# bathroomIndicator.net
KiCad netlist of a schematic drawn in EAGLE
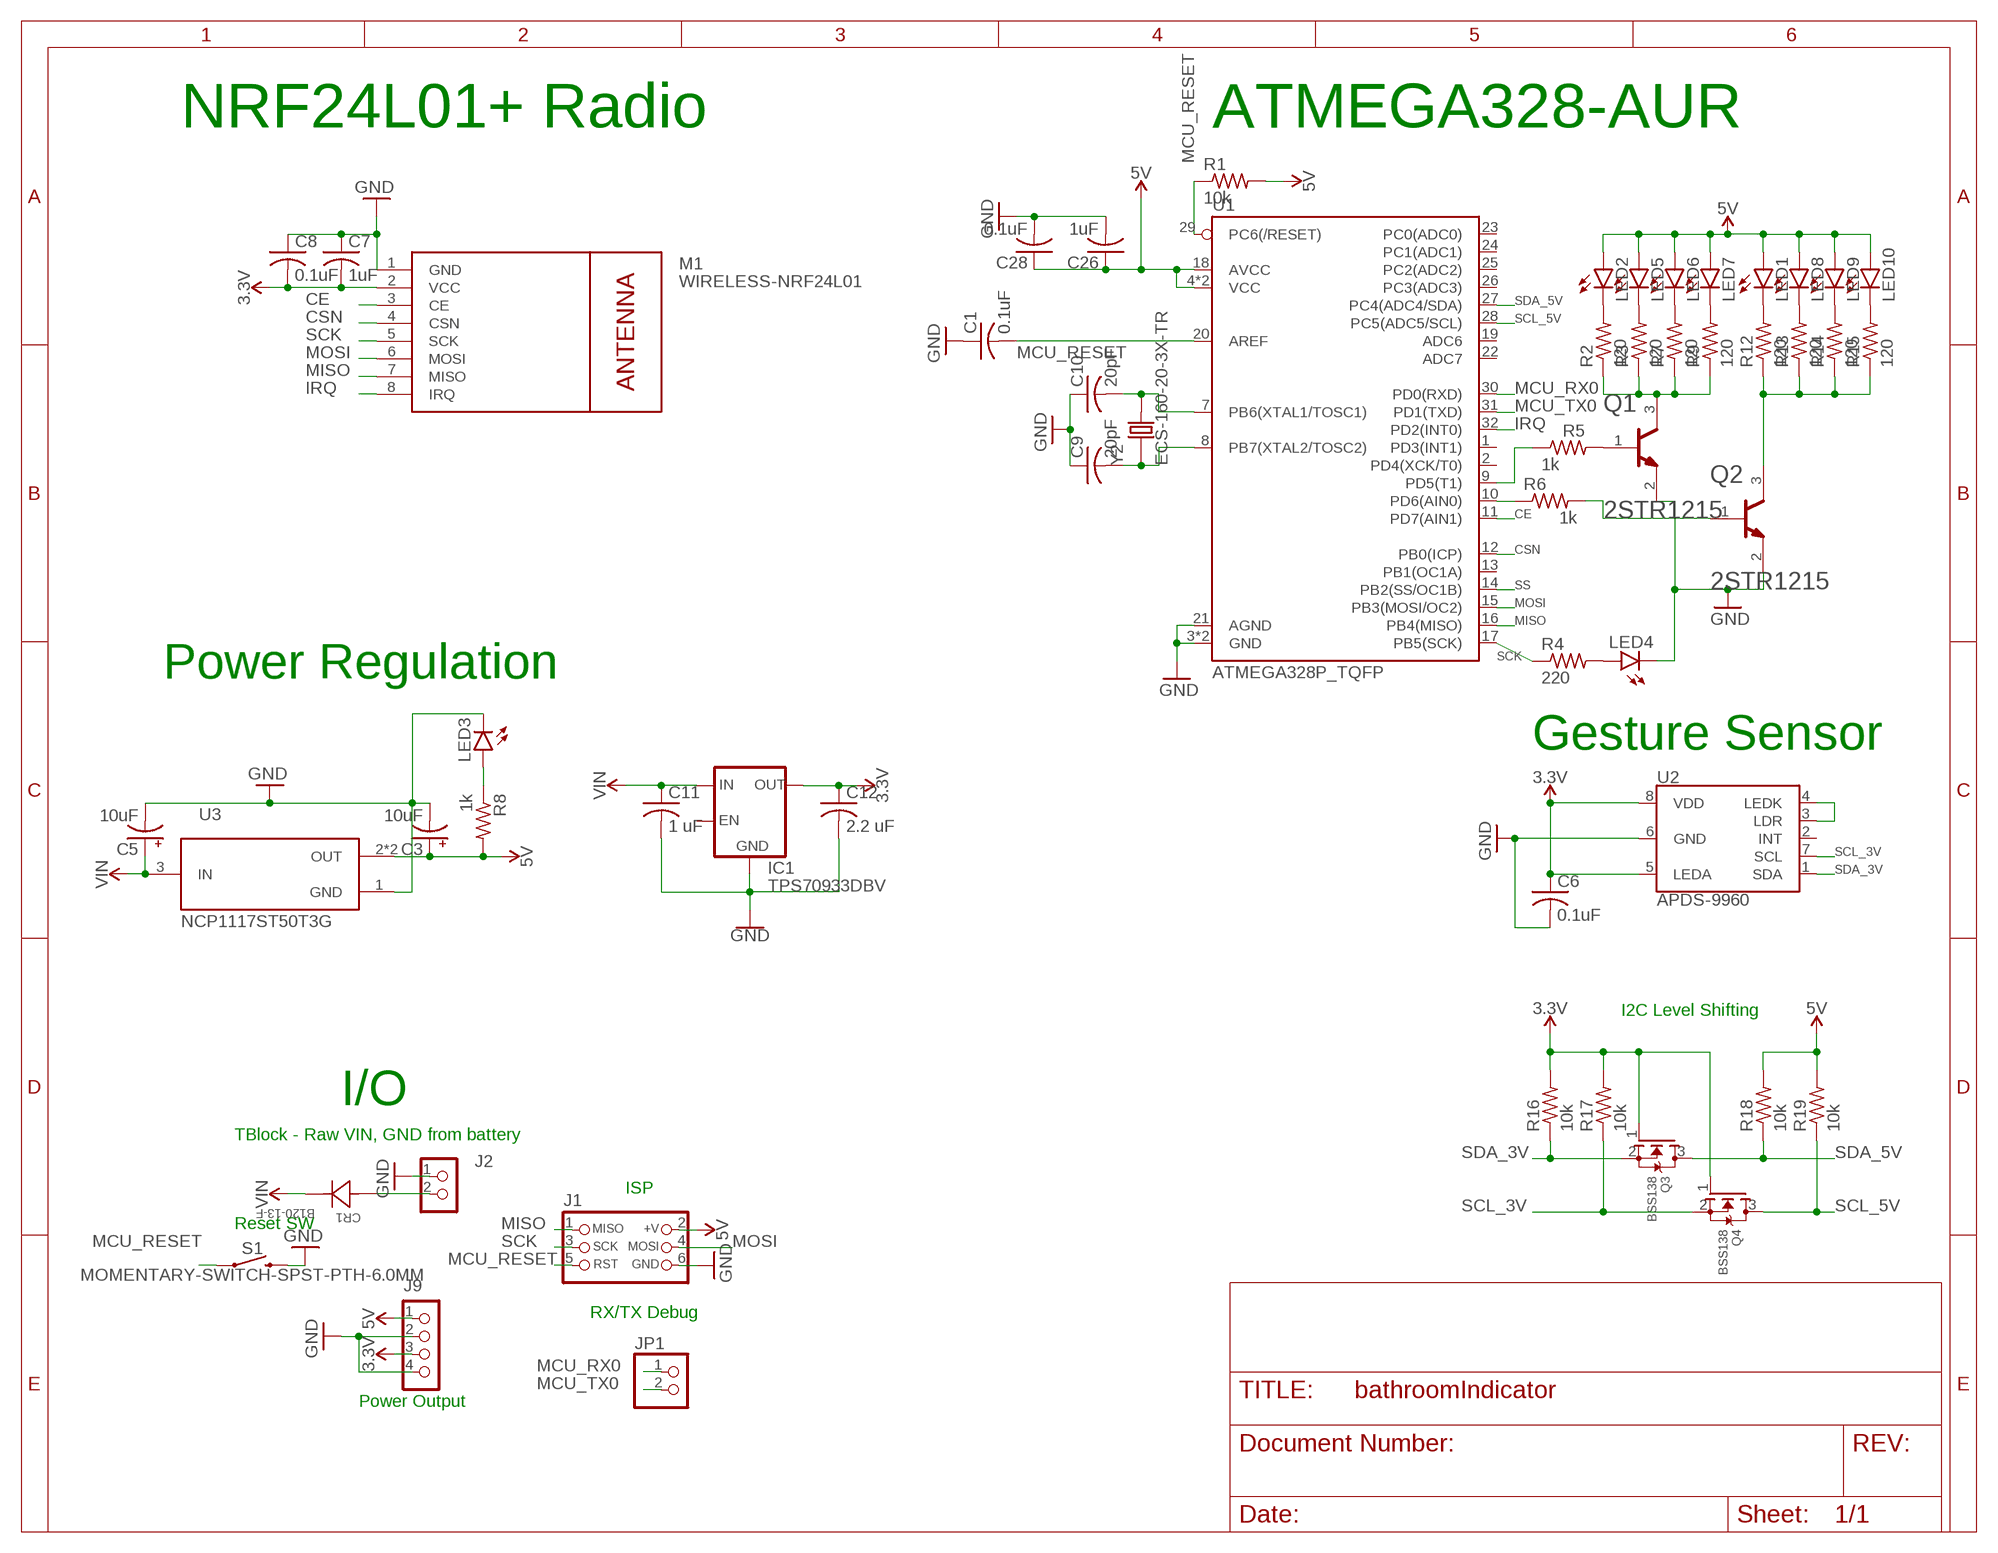
[diagram p0: schematic, sheet 1]

(export (version "E")
  (design (tool "Eeschema 10.0.6"))
  (components
    (comp (ref "C1")
      (value "0.1uF")
      (footprint "eagle-import:C0805")
      (libsource (lib "eagle-import") (part "C-USC0805"))
    )
    (comp (ref "C3")
      (value "10uF")
      (footprint "eagle-import:B_3528-21W")
      (libsource (lib "eagle-import") (part "CPOL-USB/3528-21W"))
    )
    (comp (ref "C5")
      (value "10uF")
      (footprint "eagle-import:B_3528-21W")
      (libsource (lib "eagle-import") (part "CPOL-USB/3528-21W"))
    )
    (comp (ref "C6")
      (value "0.1uF")
      (footprint "eagle-import:C0805")
      (libsource (lib "eagle-import") (part "C-USC0805"))
    )
    (comp (ref "C7")
      (value "1uF")
      (footprint "eagle-import:C0805")
      (libsource (lib "eagle-import") (part "C-USC0805"))
    )
    (comp (ref "C8")
      (value "0.1uF")
      (footprint "eagle-import:C0805")
      (libsource (lib "eagle-import") (part "C-USC0805"))
    )
    (comp (ref "C9")
      (value "20pF")
      (footprint "eagle-import:C0805")
      (libsource (lib "eagle-import") (part "C-USC0805"))
    )
    (comp (ref "C10")
      (value "20pF")
      (footprint "eagle-import:C0805")
      (libsource (lib "eagle-import") (part "C-USC0805"))
    )
    (comp (ref "C11")
      (value "1 uF")
      (footprint "eagle-import:C0805")
      (libsource (lib "eagle-import") (part "C-USC0805"))
    )
    (comp (ref "C12")
      (value "2.2 uF")
      (footprint "eagle-import:C0805")
      (libsource (lib "eagle-import") (part "C-USC0805"))
    )
    (comp (ref "C26")
      (value "1uF")
      (footprint "eagle-import:C0805")
      (libsource (lib "eagle-import") (part "C-USC0805"))
    )
    (comp (ref "C28")
      (value "0.1uF")
      (footprint "eagle-import:C0805")
      (libsource (lib "eagle-import") (part "C-USC0805"))
    )
    (comp (ref "CR1")
      (value "B120-13-F")
      (footprint "eagle-import:SMA_DIO")
      (libsource (lib "eagle-import") (part "B120-13-F"))
    )
    (comp (ref "IC1")
      (value "TPS70933DBV")
      (footprint "eagle-import:SOT23-5")
      (fields (field (name "MF") "Texas Instruments") (field (name "MPN") "TPS70933DBVT"))
      (libsource (lib "eagle-import") (part "TPS709DBV33"))
    )
    (comp (ref "J1")
      (value "CON_HEADER_PRG_AVR_ICSP-PTH")
      (footprint "eagle-import:HEADER_PRG_2X03")
      (libsource (lib "eagle-import") (part "CON_HEADER_PRG_AVR_ICSP-PTH"))
    )
    (comp (ref "J2")
      (value "CON_TERMINAL_BLOCK_02-5MM")
      (footprint "eagle-import:TERMINAL_BLOCK_2P_5")
      (libsource (lib "eagle-import") (part "CON_TERMINAL_BLOCK_02-5MM"))
    )
    (comp (ref "J9")
      (value "CON_HEADER_1X04")
      (footprint "eagle-import:M1X4")
      (libsource (lib "eagle-import") (part "CON_HEADER_1X04"))
    )
    (comp (ref "JP1")
      (value "HEADER-1X2ROUND")
      (footprint "eagle-import:1X02_ROUND")
      (libsource (lib "eagle-import") (part "HEADER-1X2ROUND"))
    )
    (comp (ref "LED1")
      (value "LED5MM")
      (footprint "eagle-import:LED5MM")
      (libsource (lib "eagle-import") (part "LED5MM"))
    )
    (comp (ref "LED2")
      (value "LED5MM")
      (footprint "eagle-import:LED5MM")
      (libsource (lib "eagle-import") (part "LED5MM"))
    )
    (comp (ref "LED3")
      (value "LEDSML0805")
      (footprint "eagle-import:SML0805")
      (libsource (lib "eagle-import") (part "LEDSML0805"))
    )
    (comp (ref "LED4")
      (value "LEDSML0805")
      (footprint "eagle-import:SML0805")
      (libsource (lib "eagle-import") (part "LEDSML0805"))
    )
    (comp (ref "LED5")
      (value "LED5MM")
      (footprint "eagle-import:LED5MM")
      (libsource (lib "eagle-import") (part "LED5MM"))
    )
    (comp (ref "LED6")
      (value "LED5MM")
      (footprint "eagle-import:LED5MM")
      (libsource (lib "eagle-import") (part "LED5MM"))
    )
    (comp (ref "LED7")
      (value "LED5MM")
      (footprint "eagle-import:LED5MM")
      (libsource (lib "eagle-import") (part "LED5MM"))
    )
    (comp (ref "LED8")
      (value "LED5MM")
      (footprint "eagle-import:LED5MM")
      (libsource (lib "eagle-import") (part "LED5MM"))
    )
    (comp (ref "LED9")
      (value "LED5MM")
      (footprint "eagle-import:LED5MM")
      (libsource (lib "eagle-import") (part "LED5MM"))
    )
    (comp (ref "LED10")
      (value "LED5MM")
      (footprint "eagle-import:LED5MM")
      (libsource (lib "eagle-import") (part "LED5MM"))
    )
    (comp (ref "M1")
      (value "WIRELESS-NRF24L01")
      (footprint "eagle-import:WIRELESS-NRF24L01")
      (libsource (lib "eagle-import") (part "WIRELESS-NRF24L01"))
    )
    (comp (ref "Q1")
      (value "STMICROELECTRONICS_2STR1215STMICROELECTRONICS_2STR1215_0_0")
      (footprint "eagle-import:STMICROELECTRONICS_2STR1215_0")
      (fields
        (field (name "DIGIKEY_PART_NUMBER") "497-6205-1-ND")
        (field (name "MF") "STMicroelectronics")
        (field (name "MOUSER_PART_NUMBER") "511-2STR1215")
      )
      (libsource (lib "eagle-import") (part "STMICROELECTRONICS_2STR1215STMICROELECTRONICS_2STR1215_0_0"))
    )
    (comp (ref "Q2")
      (value "STMICROELECTRONICS_2STR1215STMICROELECTRONICS_2STR1215_0_0")
      (footprint "eagle-import:STMICROELECTRONICS_2STR1215_0")
      (fields
        (field (name "DIGIKEY_PART_NUMBER") "497-6205-1-ND")
        (field (name "MF") "STMicroelectronics")
        (field (name "MOUSER_PART_NUMBER") "511-2STR1215")
      )
      (libsource (lib "eagle-import") (part "STMICROELECTRONICS_2STR1215STMICROELECTRONICS_2STR1215_0_0"))
    )
    (comp (ref "Q3")
      (value "BSS138")
      (footprint "eagle-import:SOT23-WIDE")
      (libsource (lib "eagle-import") (part "MOSFET-NWIDE"))
    )
    (comp (ref "Q4")
      (value "BSS138")
      (footprint "eagle-import:SOT23-WIDE")
      (libsource (lib "eagle-import") (part "MOSFET-NWIDE"))
    )
    (comp (ref "R1")
      (value "10k")
      (footprint "eagle-import:R0805")
      (libsource (lib "eagle-import") (part "R-US_R0805"))
    )
    (comp (ref "R2")
      (value "120")
      (footprint "eagle-import:R0805")
      (libsource (lib "eagle-import") (part "R-US_R0805"))
    )
    (comp (ref "R3")
      (value "120")
      (footprint "eagle-import:R0805")
      (libsource (lib "eagle-import") (part "R-US_R0805"))
    )
    (comp (ref "R4")
      (value "220")
      (footprint "eagle-import:R0805")
      (libsource (lib "eagle-import") (part "R-US_R0805"))
    )
    (comp (ref "R5")
      (value "1k")
      (footprint "eagle-import:R0805")
      (libsource (lib "eagle-import") (part "R-US_R0805"))
    )
    (comp (ref "R6")
      (value "1k")
      (footprint "eagle-import:R0805")
      (libsource (lib "eagle-import") (part "R-US_R0805"))
    )
    (comp (ref "R7")
      (value "120")
      (footprint "eagle-import:R0805")
      (libsource (lib "eagle-import") (part "R-US_R0805"))
    )
    (comp (ref "R8")
      (value "1k")
      (footprint "eagle-import:R0805")
      (libsource (lib "eagle-import") (part "R-US_R0805"))
    )
    (comp (ref "R9")
      (value "120")
      (footprint "eagle-import:R0805")
      (libsource (lib "eagle-import") (part "R-US_R0805"))
    )
    (comp (ref "R12")
      (value "120")
      (footprint "eagle-import:R0805")
      (libsource (lib "eagle-import") (part "R-US_R0805"))
    )
    (comp (ref "R13")
      (value "120")
      (footprint "eagle-import:R0805")
      (libsource (lib "eagle-import") (part "R-US_R0805"))
    )
    (comp (ref "R14")
      (value "120")
      (footprint "eagle-import:R0805")
      (libsource (lib "eagle-import") (part "R-US_R0805"))
    )
    (comp (ref "R15")
      (value "120")
      (footprint "eagle-import:R0805")
      (libsource (lib "eagle-import") (part "R-US_R0805"))
    )
    (comp (ref "R16")
      (value "10k")
      (footprint "eagle-import:R0805")
      (libsource (lib "eagle-import") (part "R-US_R0805"))
    )
    (comp (ref "R17")
      (value "10k")
      (footprint "eagle-import:R0805")
      (libsource (lib "eagle-import") (part "R-US_R0805"))
    )
    (comp (ref "R18")
      (value "10k")
      (footprint "eagle-import:R0805")
      (libsource (lib "eagle-import") (part "R-US_R0805"))
    )
    (comp (ref "R19")
      (value "10k")
      (footprint "eagle-import:R0805")
      (libsource (lib "eagle-import") (part "R-US_R0805"))
    )
    (comp (ref "S1")
      (value "MOMENTARY-SWITCH-SPST-PTH-6.0MM")
      (footprint "eagle-import:TACTILE_SWITCH_PTH_6.0MM")
      (libsource (lib "eagle-import") (part "MOMENTARY-SWITCH-SPST-PTH-6.0MM"))
    )
    (comp (ref "U1")
      (value "ATMEGA328P_TQFP")
      (footprint "eagle-import:TQFP32-08")
      (libsource (lib "eagle-import") (part "ATMEGA328P_TQFP"))
    )
    (comp (ref "U2")
      (value "APDS-9960")
      (footprint "eagle-import:APDS-9960")
      (libsource (lib "eagle-import") (part "APDS-9960"))
    )
    (comp (ref "U3")
      (value "NCP1117ST50T3G")
      (footprint "eagle-import:SOT230P700X180-4N")
      (fields (field (name "MF") "ON Semiconductor"))
      (libsource (lib "eagle-import") (part "NCP1117ST50T3G"))
    )
    (comp (ref "Y2")
      (value "ECS-160-20-3X-TR")
      (footprint "eagle-import:XTAL_ECS-160-20-3X-TR")
      (fields (field (name "MF") "ECS Inc."))
      (libsource (lib "eagle-import") (part "ECS-160-20-3X-TR"))
    )
  )
  (nets
    (net (code "1") (name "/CE") (class "Default")
      (node (ref "M1") (pin "3") (pinfunction "CE_3") (pintype "bidirectional"))
      (node (ref "U1") (pin "11") (pinfunction "PD7(AIN1)_11") (pintype "bidirectional"))
    )
    (net (code "2") (name "/CSN") (class "Default")
      (node (ref "M1") (pin "4") (pinfunction "CSN_4") (pintype "bidirectional"))
      (node (ref "U1") (pin "12") (pinfunction "PB0(ICP)_12") (pintype "bidirectional"))
    )
    (net (code "3") (name "/IRQ") (class "Default")
      (node (ref "M1") (pin "8") (pinfunction "IRQ_8") (pintype "bidirectional"))
      (node (ref "U1") (pin "32") (pinfunction "PD2(INT0)_32") (pintype "bidirectional"))
    )
    (net (code "4") (name "/MCU_RESET") (class "Default")
      (node (ref "J1") (pin "5") (pinfunction "RST_5") (pintype "passive"))
      (node (ref "R1") (pin "1") (pinfunction "1_1") (pintype "passive"))
      (node (ref "S1") (pin "1") (pinfunction "1_1") (pintype "passive"))
      (node (ref "U1") (pin "29") (pinfunction "PC6(/RESET)_29") (pintype "bidirectional"))
    )
    (net (code "5") (name "/MCU_RX0") (class "Default")
      (node (ref "JP1") (pin "1") (pinfunction "1_1") (pintype "passive"))
      (node (ref "U1") (pin "30") (pinfunction "PD0(RXD)_30") (pintype "bidirectional"))
    )
    (net (code "6") (name "/MCU_TX0") (class "Default")
      (node (ref "JP1") (pin "2") (pinfunction "2_2") (pintype "passive"))
      (node (ref "U1") (pin "31") (pinfunction "PD1(TXD)_31") (pintype "bidirectional"))
    )
    (net (code "7") (name "/MISO") (class "Default")
      (node (ref "J1") (pin "1") (pinfunction "MISO_1") (pintype "passive"))
      (node (ref "M1") (pin "7") (pinfunction "MISO_7") (pintype "bidirectional"))
      (node (ref "U1") (pin "16") (pinfunction "PB4(MISO)_16") (pintype "bidirectional"))
    )
    (net (code "8") (name "/MOSI") (class "Default")
      (node (ref "J1") (pin "4") (pinfunction "MOSI_4") (pintype "passive"))
      (node (ref "M1") (pin "6") (pinfunction "MOSI_6") (pintype "bidirectional"))
      (node (ref "U1") (pin "15") (pinfunction "PB3(MOSI/OC2)_15") (pintype "bidirectional"))
    )
    (net (code "9") (name "/SCK") (class "Default")
      (node (ref "J1") (pin "3") (pinfunction "SCK_3") (pintype "passive"))
      (node (ref "M1") (pin "5") (pinfunction "SCK_5") (pintype "bidirectional"))
      (node (ref "R4") (pin "1") (pinfunction "1_1") (pintype "passive"))
      (node (ref "U1") (pin "17") (pinfunction "PB5(SCK)_17") (pintype "bidirectional"))
    )
    (net (code "10") (name "/SCL_3V") (class "Default")
      (node (ref "Q4") (pin "2") (pinfunction "S_2") (pintype "bidirectional"))
      (node (ref "R17") (pin "1") (pinfunction "1_1") (pintype "passive"))
      (node (ref "U2") (pin "7") (pinfunction "SCL_7") (pintype "bidirectional"))
    )
    (net (code "11") (name "/SCL_5V") (class "Default")
      (node (ref "Q4") (pin "3") (pinfunction "D_3") (pintype "bidirectional"))
      (node (ref "R19") (pin "1") (pinfunction "1_1") (pintype "passive"))
      (node (ref "U1") (pin "28") (pinfunction "PC5(ADC5/SCL)_28") (pintype "bidirectional"))
    )
    (net (code "12") (name "/SDA_3V") (class "Default")
      (node (ref "Q3") (pin "2") (pinfunction "S_2") (pintype "bidirectional"))
      (node (ref "R16") (pin "1") (pinfunction "1_1") (pintype "passive"))
      (node (ref "U2") (pin "1") (pinfunction "SDA_1") (pintype "bidirectional"))
    )
    (net (code "13") (name "/SDA_5V") (class "Default")
      (node (ref "Q3") (pin "3") (pinfunction "D_3") (pintype "bidirectional"))
      (node (ref "R18") (pin "1") (pinfunction "1_1") (pintype "passive"))
      (node (ref "U1") (pin "27") (pinfunction "PC4(ADC4/SDA)_27") (pintype "bidirectional"))
    )
    (net (code "14") (name "/SS") (class "Default")
      (node (ref "U1") (pin "14") (pinfunction "PB2(SS/OC1B)_14") (pintype "bidirectional"))
    )
    (net (code "15") (name "3.3V") (class "Default")
      (node (ref "C12") (pin "1") (pinfunction "1_1") (pintype "passive"))
      (node (ref "C6") (pin "1") (pinfunction "1_1") (pintype "passive"))
      (node (ref "C7") (pin "2") (pinfunction "2_2") (pintype "passive"))
      (node (ref "C8") (pin "2") (pinfunction "2_2") (pintype "passive"))
      (node (ref "IC1") (pin "5") (pinfunction "OUT_5") (pintype "passive"))
      (node (ref "J9") (pin "3") (pinfunction "3_3") (pintype "bidirectional"))
      (node (ref "M1") (pin "2") (pinfunction "VCC_2") (pintype "power_in"))
      (node (ref "Q3") (pin "1") (pinfunction "G_1") (pintype "bidirectional"))
      (node (ref "Q4") (pin "1") (pinfunction "G_1") (pintype "bidirectional"))
      (node (ref "R16") (pin "2") (pinfunction "2_2") (pintype "passive"))
      (node (ref "R17") (pin "2") (pinfunction "2_2") (pintype "passive"))
      (node (ref "U2") (pin "5") (pinfunction "LEDA_5") (pintype "bidirectional"))
      (node (ref "U2") (pin "8") (pinfunction "VDD_8") (pintype "bidirectional"))
    )
    (net (code "16") (name "5V") (class "Default")
      (node (ref "C26") (pin "1") (pinfunction "1_1") (pintype "passive"))
      (node (ref "C28") (pin "1") (pinfunction "1_1") (pintype "passive"))
      (node (ref "C3") (pin "+") (pinfunction "+_+") (pintype "passive"))
      (node (ref "J1") (pin "2") (pinfunction "+V_2") (pintype "passive"))
      (node (ref "J9") (pin "1") (pinfunction "1_1") (pintype "bidirectional"))
      (node (ref "LED1") (pin "A") (pinfunction "A_A") (pintype "passive"))
      (node (ref "LED10") (pin "A") (pinfunction "A_A") (pintype "passive"))
      (node (ref "LED2") (pin "A") (pinfunction "A_A") (pintype "passive"))
      (node (ref "LED5") (pin "A") (pinfunction "A_A") (pintype "passive"))
      (node (ref "LED6") (pin "A") (pinfunction "A_A") (pintype "passive"))
      (node (ref "LED7") (pin "A") (pinfunction "A_A") (pintype "passive"))
      (node (ref "LED8") (pin "A") (pinfunction "A_A") (pintype "passive"))
      (node (ref "LED9") (pin "A") (pinfunction "A_A") (pintype "passive"))
      (node (ref "R1") (pin "2") (pinfunction "2_2") (pintype "passive"))
      (node (ref "R18") (pin "2") (pinfunction "2_2") (pintype "passive"))
      (node (ref "R19") (pin "2") (pinfunction "2_2") (pintype "passive"))
      (node (ref "R8") (pin "2") (pinfunction "2_2") (pintype "passive"))
      (node (ref "U1") (pin "18") (pinfunction "AVCC_18") (pintype "bidirectional"))
      (node (ref "U1") (pin "4") (pinfunction "VCC_4") (pintype "bidirectional"))
      (node (ref "U1") (pin "6") (pinfunction "VCC_6") (pintype "bidirectional"))
      (node (ref "U3") (pin "2") (pinfunction "OUT_2") (pintype "output"))
      (node (ref "U3") (pin "4") (pinfunction "OUT_4") (pintype "output"))
    )
    (net (code "17") (name "GND") (class "Default")
      (node (ref "C1") (pin "1") (pinfunction "1_1") (pintype "passive"))
      (node (ref "C10") (pin "1") (pinfunction "1_1") (pintype "passive"))
      (node (ref "C11") (pin "2") (pinfunction "2_2") (pintype "passive"))
      (node (ref "C12") (pin "2") (pinfunction "2_2") (pintype "passive"))
      (node (ref "C26") (pin "2") (pinfunction "2_2") (pintype "passive"))
      (node (ref "C28") (pin "2") (pinfunction "2_2") (pintype "passive"))
      (node (ref "C3") (pin "-") (pinfunction "-_-") (pintype "passive"))
      (node (ref "C5") (pin "-") (pinfunction "-_-") (pintype "passive"))
      (node (ref "C6") (pin "2") (pinfunction "2_2") (pintype "passive"))
      (node (ref "C7") (pin "1") (pinfunction "1_1") (pintype "passive"))
      (node (ref "C8") (pin "1") (pinfunction "1_1") (pintype "passive"))
      (node (ref "C9") (pin "1") (pinfunction "1_1") (pintype "passive"))
      (node (ref "IC1") (pin "2") (pinfunction "GND_2") (pintype "input"))
      (node (ref "J1") (pin "6") (pinfunction "GND_6") (pintype "passive"))
      (node (ref "J2") (pin "1") (pinfunction "1_1") (pintype "passive"))
      (node (ref "J9") (pin "2") (pinfunction "2_2") (pintype "bidirectional"))
      (node (ref "J9") (pin "4") (pinfunction "4_4") (pintype "bidirectional"))
      (node (ref "LED3") (pin "C") (pinfunction "C_C") (pintype "passive"))
      (node (ref "LED4") (pin "C") (pinfunction "C_C") (pintype "passive"))
      (node (ref "M1") (pin "1") (pinfunction "GND_1") (pintype "power_in"))
      (node (ref "Q1") (pin "2") (pinfunction "E_2") (pintype "passive"))
      (node (ref "Q2") (pin "2") (pinfunction "E_2") (pintype "passive"))
      (node (ref "S1") (pin "3") (pinfunction "2_3") (pintype "passive"))
      (node (ref "U1") (pin "21") (pinfunction "AGND_21") (pintype "bidirectional"))
      (node (ref "U1") (pin "3") (pinfunction "GND_3") (pintype "bidirectional"))
      (node (ref "U1") (pin "5") (pinfunction "GND_5") (pintype "bidirectional"))
      (node (ref "U2") (pin "6") (pinfunction "GND_6") (pintype "bidirectional"))
      (node (ref "U3") (pin "1") (pinfunction "GND_1") (pintype "power_in"))
    )
    (net (code "18") (name "Net-(CR1-Pad2)") (class "Default")
      (node (ref "CR1") (pin "2") (pinfunction "2_2") (pintype "passive"))
      (node (ref "J2") (pin "2") (pinfunction "2_2") (pintype "passive"))
    )
    (net (code "19") (name "Net-(LED1-C)") (class "Default")
      (node (ref "LED1") (pin "K") (pinfunction "C_K") (pintype "passive"))
      (node (ref "R12") (pin "2") (pinfunction "2_2") (pintype "passive"))
    )
    (net (code "20") (name "Net-(LED2-C)") (class "Default")
      (node (ref "LED2") (pin "K") (pinfunction "C_K") (pintype "passive"))
      (node (ref "R2") (pin "2") (pinfunction "2_2") (pintype "passive"))
    )
    (net (code "21") (name "Net-(LED3-PadA)") (class "Default")
      (node (ref "LED3") (pin "A") (pinfunction "A_A") (pintype "passive"))
      (node (ref "R8") (pin "1") (pinfunction "1_1") (pintype "passive"))
    )
    (net (code "22") (name "Net-(LED4-PadA)") (class "Default")
      (node (ref "LED4") (pin "A") (pinfunction "A_A") (pintype "passive"))
      (node (ref "R4") (pin "2") (pinfunction "2_2") (pintype "passive"))
    )
    (net (code "23") (name "Net-(LED5-C)") (class "Default")
      (node (ref "LED5") (pin "K") (pinfunction "C_K") (pintype "passive"))
      (node (ref "R3") (pin "2") (pinfunction "2_2") (pintype "passive"))
    )
    (net (code "24") (name "Net-(LED6-C)") (class "Default")
      (node (ref "LED6") (pin "K") (pinfunction "C_K") (pintype "passive"))
      (node (ref "R7") (pin "2") (pinfunction "2_2") (pintype "passive"))
    )
    (net (code "25") (name "Net-(LED7-C)") (class "Default")
      (node (ref "LED7") (pin "K") (pinfunction "C_K") (pintype "passive"))
      (node (ref "R9") (pin "2") (pinfunction "2_2") (pintype "passive"))
    )
    (net (code "26") (name "Net-(LED8-C)") (class "Default")
      (node (ref "LED8") (pin "K") (pinfunction "C_K") (pintype "passive"))
      (node (ref "R13") (pin "2") (pinfunction "2_2") (pintype "passive"))
    )
    (net (code "27") (name "Net-(LED9-C)") (class "Default")
      (node (ref "LED9") (pin "K") (pinfunction "C_K") (pintype "passive"))
      (node (ref "R14") (pin "2") (pinfunction "2_2") (pintype "passive"))
    )
    (net (code "28") (name "Net-(LED10-C)") (class "Default")
      (node (ref "LED10") (pin "K") (pinfunction "C_K") (pintype "passive"))
      (node (ref "R15") (pin "2") (pinfunction "2_2") (pintype "passive"))
    )
    (net (code "29") (name "Net-(Q1-B)") (class "Default")
      (node (ref "Q1") (pin "1") (pinfunction "B_1") (pintype "passive"))
      (node (ref "R5") (pin "2") (pinfunction "2_2") (pintype "passive"))
    )
    (net (code "30") (name "Net-(Q1-C)") (class "Default")
      (node (ref "Q1") (pin "3") (pinfunction "C_3") (pintype "passive"))
      (node (ref "R2") (pin "1") (pinfunction "1_1") (pintype "passive"))
      (node (ref "R3") (pin "1") (pinfunction "1_1") (pintype "passive"))
      (node (ref "R7") (pin "1") (pinfunction "1_1") (pintype "passive"))
      (node (ref "R9") (pin "1") (pinfunction "1_1") (pintype "passive"))
    )
    (net (code "31") (name "Net-(Q2-B)") (class "Default")
      (node (ref "Q2") (pin "1") (pinfunction "B_1") (pintype "passive"))
      (node (ref "R6") (pin "2") (pinfunction "2_2") (pintype "passive"))
    )
    (net (code "32") (name "Net-(Q2-C)") (class "Default")
      (node (ref "Q2") (pin "3") (pinfunction "C_3") (pintype "passive"))
      (node (ref "R12") (pin "1") (pinfunction "1_1") (pintype "passive"))
      (node (ref "R13") (pin "1") (pinfunction "1_1") (pintype "passive"))
      (node (ref "R14") (pin "1") (pinfunction "1_1") (pintype "passive"))
      (node (ref "R15") (pin "1") (pinfunction "1_1") (pintype "passive"))
    )
    (net (code "33") (name "Net-(U1-AREF)") (class "Default")
      (node (ref "C1") (pin "2") (pinfunction "2_2") (pintype "passive"))
      (node (ref "U1") (pin "20") (pinfunction "AREF_20") (pintype "bidirectional"))
    )
    (net (code "34") (name "Net-(U1-PB6(XTAL1{slash}TOSC1))") (class "Default")
      (node (ref "C10") (pin "2") (pinfunction "2_2") (pintype "passive"))
      (node (ref "U1") (pin "7") (pinfunction "PB6(XTAL1/TOSC1)_7") (pintype "bidirectional"))
      (node (ref "Y2") (pin "2") (pinfunction "2_2") (pintype "passive"))
    )
    (net (code "35") (name "Net-(U1-PB7(XTAL2{slash}TOSC2))") (class "Default")
      (node (ref "C9") (pin "2") (pinfunction "2_2") (pintype "passive"))
      (node (ref "U1") (pin "8") (pinfunction "PB7(XTAL2/TOSC2)_8") (pintype "bidirectional"))
      (node (ref "Y2") (pin "1") (pinfunction "1_1") (pintype "passive"))
    )
    (net (code "36") (name "Net-(U1-PD5(T1))") (class "Default")
      (node (ref "R5") (pin "1") (pinfunction "1_1") (pintype "passive"))
      (node (ref "U1") (pin "9") (pinfunction "PD5(T1)_9") (pintype "bidirectional"))
    )
    (net (code "37") (name "Net-(U1-PD6(AIN0))") (class "Default")
      (node (ref "R6") (pin "1") (pinfunction "1_1") (pintype "passive"))
      (node (ref "U1") (pin "10") (pinfunction "PD6(AIN0)_10") (pintype "bidirectional"))
    )
    (net (code "38") (name "Net-(U2-LDR)") (class "Default")
      (node (ref "U2") (pin "3") (pinfunction "LDR_3") (pintype "bidirectional"))
      (node (ref "U2") (pin "4") (pinfunction "LEDK_4") (pintype "bidirectional"))
    )
    (net (code "39") (name "VIN") (class "Default")
      (node (ref "C11") (pin "1") (pinfunction "1_1") (pintype "passive"))
      (node (ref "C5") (pin "+") (pinfunction "+_+") (pintype "passive"))
      (node (ref "CR1") (pin "1") (pinfunction "1_1") (pintype "passive"))
      (node (ref "IC1") (pin "1") (pinfunction "IN_1") (pintype "input"))
      (node (ref "U3") (pin "3") (pinfunction "IN_3") (pintype "input"))
    )
    (net (code "40") (name "unconnected-(IC1-EN-Pad3)") (class "Default")
      (node (ref "IC1") (pin "3") (pinfunction "EN_3") (pintype "input"))
    )
    (net (code "41") (name "unconnected-(U1-ADC6-Pad19)") (class "Default")
      (node (ref "U1") (pin "19") (pinfunction "ADC6_19") (pintype "bidirectional"))
    )
    (net (code "42") (name "unconnected-(U1-ADC7-Pad22)") (class "Default")
      (node (ref "U1") (pin "22") (pinfunction "ADC7_22") (pintype "bidirectional"))
    )
    (net (code "43") (name "unconnected-(U1-PB1(OC1A)-Pad13)") (class "Default")
      (node (ref "U1") (pin "13") (pinfunction "PB1(OC1A)_13") (pintype "bidirectional"))
    )
    (net (code "44") (name "unconnected-(U1-PC0(ADC0)-Pad23)") (class "Default")
      (node (ref "U1") (pin "23") (pinfunction "PC0(ADC0)_23") (pintype "bidirectional"))
    )
    (net (code "45") (name "unconnected-(U1-PC1(ADC1)-Pad24)") (class "Default")
      (node (ref "U1") (pin "24") (pinfunction "PC1(ADC1)_24") (pintype "bidirectional"))
    )
    (net (code "46") (name "unconnected-(U1-PC2(ADC2)-Pad25)") (class "Default")
      (node (ref "U1") (pin "25") (pinfunction "PC2(ADC2)_25") (pintype "bidirectional"))
    )
    (net (code "47") (name "unconnected-(U1-PC3(ADC3)-Pad26)") (class "Default")
      (node (ref "U1") (pin "26") (pinfunction "PC3(ADC3)_26") (pintype "bidirectional"))
    )
    (net (code "48") (name "unconnected-(U1-PD3(INT1)-Pad1)") (class "Default")
      (node (ref "U1") (pin "1") (pinfunction "PD3(INT1)_1") (pintype "bidirectional"))
    )
    (net (code "49") (name "unconnected-(U1-PD4(XCK{slash}T0)-Pad2)") (class "Default")
      (node (ref "U1") (pin "2") (pinfunction "PD4(XCK/T0)_2") (pintype "bidirectional"))
    )
    (net (code "50") (name "unconnected-(U2-INT-Pad2)") (class "Default")
      (node (ref "U2") (pin "2") (pinfunction "INT_2") (pintype "bidirectional"))
    )
  )
)
